# Power_Stage.net
KiCad netlist of a schematic drawn in Altium Designer
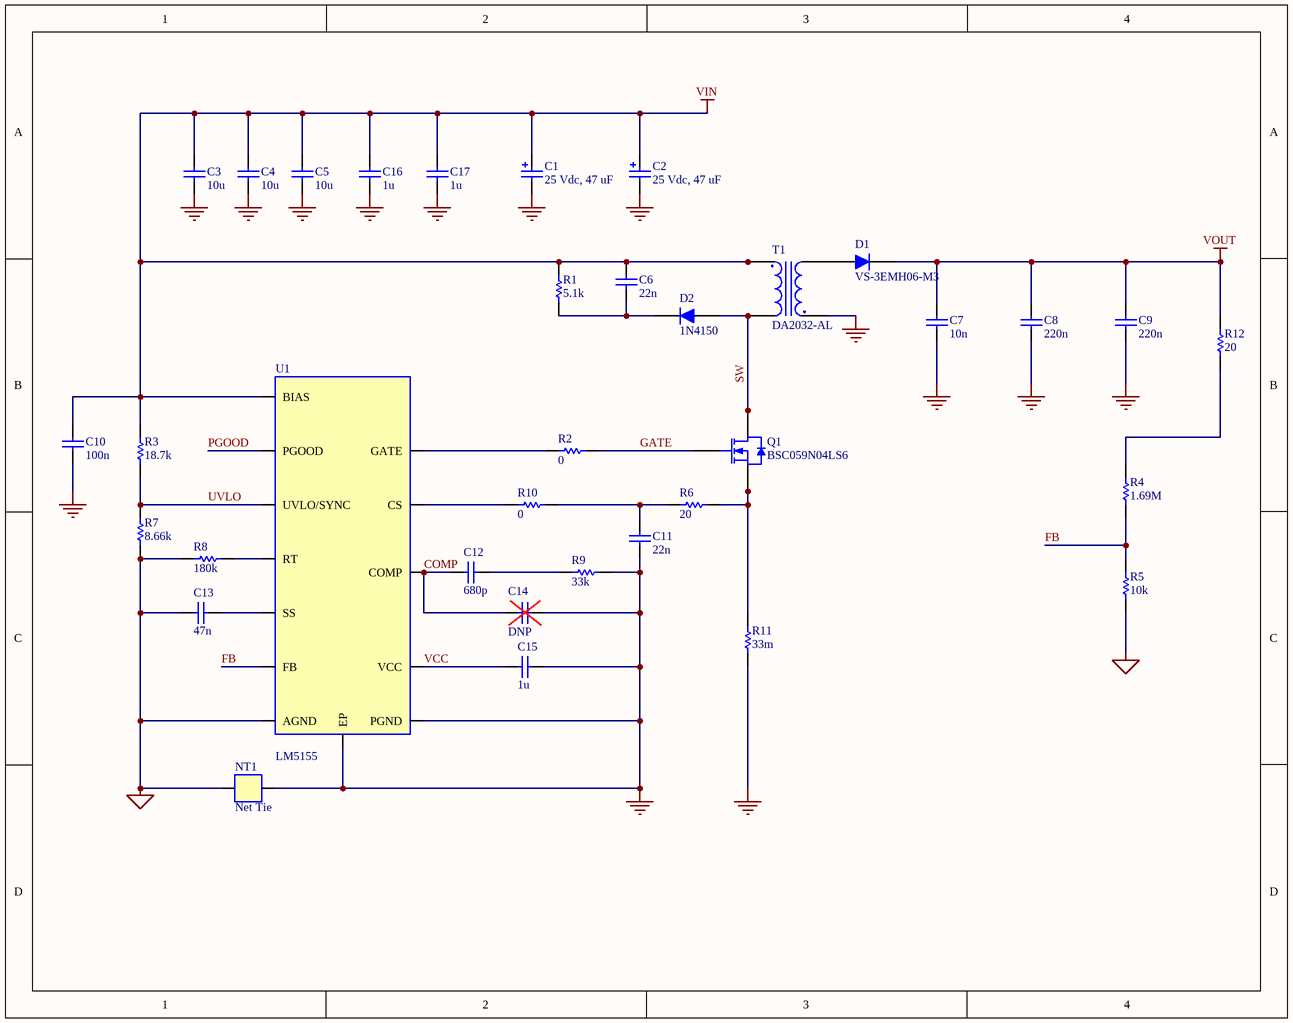
[diagram p0: Power Stage.SchDoc]

(export (version "E")
  (design (tool "Eeschema 10.0.6"))
  (components
    (comp (ref "C1")
      (value "25 Vdc, 47 uF")
      (footprint "WCAP-PTG5_8x8x3.5")
      (description "WCAP-PTG5 Aluminum Polymer Capacitors, 8x8mm, 25 Vdc, 47 uF")
      (fields (field (name "PART NUMBER") "870025574002") (field (name "PUBLISHER") "Wurth Elektronik"))
      (libsource (lib "ALTIUM-WCAP-PTG5-rev17a") (part "870025574002"))
    )
    (comp (ref "C2")
      (value "25 Vdc, 47 uF")
      (footprint "WCAP-PTG5_8x8x3.5")
      (description "WCAP-PTG5 Aluminum Polymer Capacitors, 8x8mm, 25 Vdc, 47 uF")
      (fields (field (name "PART NUMBER") "870025574002") (field (name "PUBLISHER") "Wurth Elektronik"))
      (libsource (lib "ALTIUM-WCAP-PTG5-rev17a") (part "870025574002"))
    )
    (comp (ref "C3")
      (value "10u")
      (footprint "CAPC1210(3225)280_N")
      (description "CAP CER 10UF 50V X7R 1210")
      (fields
        (field (name "MANUFACTURER") "Samsung")
        (field (name "MANUFACTURER PART NUMBER") "CL32B106KBJNNWE")
      )
      (libsource (lib "Misc Caps") (part "CL32B106KBJNNWE"))
    )
    (comp (ref "C4")
      (value "10u")
      (footprint "CAPC1210(3225)280_N")
      (description "CAP CER 10UF 50V X7R 1210")
      (fields
        (field (name "MANUFACTURER") "Samsung")
        (field (name "MANUFACTURER PART NUMBER") "CL32B106KBJNNWE")
      )
      (libsource (lib "Misc Caps") (part "CL32B106KBJNNWE"))
    )
    (comp (ref "C5")
      (value "10u")
      (footprint "CAPC1210(3225)280_N")
      (description "CAP CER 10UF 50V X7R 1210")
      (fields
        (field (name "MANUFACTURER") "Samsung")
        (field (name "MANUFACTURER PART NUMBER") "CL32B106KBJNNWE")
      )
      (libsource (lib "Misc Caps") (part "CL32B106KBJNNWE"))
    )
    (comp (ref "C6")
      (value "22n")
      (footprint "CAPC0805(2012)100_M")
      (description "CAP CER 0.022UF 100V X7R 0805")
      (fields
        (field (name "MANUFACTURER") "Yageo")
        (field (name "MANUFACTURER PART NUMBER") "CC0805KRX7R0BB223")
      )
      (libsource (lib "0805 Caps") (part "CC0805KRX7R0BB223"))
    )
    (comp (ref "C7")
      (value "10n")
      (footprint "CAPC1206(3216)170_M")
      (description "CAP CER 10000PF 250V C0GNP0 1206")
      (fields
        (field (name "MANUFACTURER") "TDK")
        (field (name "MANUFACTURER PART NUMBER") "C3216C0G2E103J115AE")
      )
      (libsource (lib "Misc Caps") (part "C3216C0G2E103J115AE"))
    )
    (comp (ref "C8")
      (value "220n")
      (footprint "WIMA 6x12x13")
      (description "Film Capacitors 250V .22uF 10% PCM10")
      (fields
        (field (name "MANUFACTURER") "WIMA")
        (field (name "MANUFACTURER PART NUMBER") "MKP4F032203G00KSSD")
      )
      (libsource (lib "Misc Caps") (part "MKP4F032203G00KSSD"))
    )
    (comp (ref "C9")
      (value "220n")
      (footprint "WIMA 6x12x13")
      (description "Film Capacitors 250V .22uF 10% PCM10")
      (fields
        (field (name "MANUFACTURER") "WIMA")
        (field (name "MANUFACTURER PART NUMBER") "MKP4F032203G00KSSD")
      )
      (libsource (lib "Misc Caps") (part "MKP4F032203G00KSSD"))
    )
    (comp (ref "C10")
      (value "100n")
      (footprint "CAPC0603(1608)100_N")
      (description "Cap Ceramic 0.1uF 50V X7R 5% SMD 0603 125C Paper T/R")
      (fields
        (field (name "MANUFACTURER") "Yageo")
        (field (name "MANUFACTURER PART NUMBER") "CC0603JRX7R9BB104")
      )
      (libsource (lib "0603 Caps") (part "CC0603JRX7R9BB104"))
    )
    (comp (ref "C11")
      (value "22n")
      (footprint "CAPC0603(1608)100_N")
      (description "Cap Ceramic 0.022uF 16V X7R 10% SMD 0603 125°C Paper T/R")
      (fields
        (field (name "MANUFACTURER") "KEMET")
        (field (name "MANUFACTURER PART NUMBER") "C0603C223K4RACTU")
      )
      (libsource (lib "0603 Caps") (part "C0603C223K4RACTU"))
    )
    (comp (ref "C12")
      (value "680p")
      (footprint "CAPC0603(1608)100_M")
      (description "Cap, Mlcc, C0g, 680Pf, 10V, 0603")
      (fields
        (field (name "MANUFACTURER") "Wurth Electronics")
        (field (name "MANUFACTURER PART NUMBER") "885012006013")
      )
      (libsource (lib "0603 Caps") (part "885012006013"))
    )
    (comp (ref "C13")
      (value "47n")
      (footprint "CAPC0603(1608)100_N")
      (description "CAP CER 0.047UF 50V X7R 0603")
      (fields
        (field (name "MANUFACTURER") "Yageo")
        (field (name "MANUFACTURER PART NUMBER") "CC0603KRX7R9BB473")
      )
      (libsource (lib "0603 Caps") (part "CC0603KRX7R9BB473"))
    )
    (comp (ref "C14")
      (value "DNP")
      (footprint "CAPC0603(1608)100_M")
      (libsource (lib "0603 Caps") (part "0603 DNP JUMPER"))
    )
    (comp (ref "C15")
      (value "1u")
      (footprint "CAPC0603(1608)100_L")
      (description "CAP CER 1UF 16V X7R 0603")
      (fields
        (field (name "MANUFACTURER") "Samsung Electro-Mechanics")
        (field (name "MANUFACTURER PART NUMBER") "CL10B105MO8NNWC")
      )
      (libsource (lib "0603 Caps") (part "CL10B105MO8NNWC"))
    )
    (comp (ref "C16")
      (value "1u")
      (footprint "CAPC0805(2012)145_N")
      (description "Cap Ceramic 1uF 50V X7R 10% SMD 0805 125C Blister T/R")
      (fields
        (field (name "MANUFACTURER") "Yageo")
        (field (name "MANUFACTURER PART NUMBER") "CC0805KKX7R9BB105")
      )
      (libsource (lib "0805 Caps") (part "CC0805KKX7R9BB105"))
    )
    (comp (ref "C17")
      (value "1u")
      (footprint "CAPC0805(2012)145_N")
      (description "Cap Ceramic 1uF 50V X7R 10% SMD 0805 125C Blister T/R")
      (fields
        (field (name "MANUFACTURER") "Yageo")
        (field (name "MANUFACTURER PART NUMBER") "CC0805KKX7R9BB105")
      )
      (libsource (lib "0805 Caps") (part "CC0805KKX7R9BB105"))
    )
    (comp (ref "D1")
      (value "VS-3EMH06-M3")
      (footprint "SMA DO-214AC")
      (description "Rectifiers 3 Amp 600 Volts Hyperfast - Low QRR")
      (fields
        (field (name "MANUFACTURER") "Vishay Semiconductors")
        (field (name "MANUFACTURER PART NUMBER") "VS-3EMH06-M3/5AT")
      )
      (libsource (lib "Discretes") (part "VS-3EMH06-M3/5AT"))
    )
    (comp (ref "D2")
      (value "1N4150")
      (footprint "SOD123")
      (description "DIODE GEN PURP 50V 200MA SOD123")
      (fields
        (field (name "MANUFACTURER") "Vishay Semiconductors")
        (field (name "MANUFACTURER PART NUMBER") "1N4150W-E3-08")
      )
      (libsource (lib "Discretes") (part "1N4150W-E3-08"))
    )
    (comp (ref "NT1")
      (value "Net Tie")
      (footprint "NET TIE .25mm")
      (libsource (lib "Connectors") (part "NET TIE"))
    )
    (comp (ref "Q1")
      (value "BSC059N04LS6")
      (footprint "PG-TDSON-8")
      (description "MOSFET N-CH 40V 59A")
      (fields
        (field (name "MANUFACTURER") "Infineon")
        (field (name "MANUFACTURER PART NUMBER") "BSC059N04LS6ATMA1")
      )
      (libsource (lib "Discretes") (part "BSC059N04LS6ATMA1"))
    )
    (comp (ref "R1")
      (value "5.1k")
      (footprint "RESC1210(3225)_M")
      (description "RES SMD 5.1K OHM 5% 1/2W 1210")
      (fields
        (field (name "MANUFACTURER") "Panasonic")
        (field (name "MANUFACTURER PART NUMBER") "ERJ-14YJ512U")
      )
      (libsource (lib "Misc resistors") (part "ERJ-14YJ512U"))
    )
    (comp (ref "R2")
      (value "0")
      (footprint "RESC0603(1608)_M")
      (description "RES SMD 0 OHM JUMPER 1/10W 0603")
      (fields
        (field (name "MANUFACTURER") "Yageo")
        (field (name "MANUFACTURER PART NUMBER") "RC0603FR-070RL")
      )
      (libsource (lib "0603 Resistors") (part "RC0603FR-070RL"))
    )
    (comp (ref "R3")
      (value "18.7k")
      (footprint "RESC0603(1608)_N")
      (description "RC Series 0603 0.1 W 18.7 kOhms 1% ±100 ppm/°C SMT Thick Film Chip Resistor")
      (fields
        (field (name "MANUFACTURER") "Yageo")
        (field (name "MANUFACTURER PART NUMBER") "RC0603FR-0718K7L")
      )
      (libsource (lib "0603 Resistors") (part "RC0603FR-0718K7L"))
    )
    (comp (ref "R4")
      (value "1.69M")
      (footprint "RESC0603(1608)_N")
      (description "Res Thick Film 0603 1.69M Ohm 1% 1/10W 100ppm/C Molded SMD Paper T/R")
      (fields
        (field (name "MANUFACTURER") "Yageo")
        (field (name "MANUFACTURER PART NUMBER") "RC0603FR-071M69L")
      )
      (libsource (lib "0603 Resistors") (part "RC0603FR-071M69L"))
    )
    (comp (ref "R5")
      (value "10k")
      (footprint "RESC0603(1608)_N")
      (description "RES SMD 10K OHM 1% 1/10W 0603")
      (fields
        (field (name "MANUFACTURER") "Yageo")
        (field (name "MANUFACTURER PART NUMBER") "RC0603FR-0710KL")
      )
      (libsource (lib "0603 Resistors") (part "RC0603FR-0710KL"))
    )
    (comp (ref "R6")
      (value "20")
      (footprint "RESC0603(1608)_N")
      (description "RES SMD 20 OHM 1% 1/10W 0603")
      (fields
        (field (name "MANUFACTURER") "Yageo")
        (field (name "MANUFACTURER PART NUMBER") "RC0603FR-0720RL")
      )
      (libsource (lib "0603 Resistors") (part "RC0603FR-0720RL"))
    )
    (comp (ref "R7")
      (value "8.66k")
      (footprint "RESC0603(1608)_N")
      (description "Res Thick Film 0603 8.66K Ohm 1% 0.1W(1/10W) ±100ppm/C Epoxy Pad SMD T/R")
      (fields
        (field (name "MANUFACTURER") "Yageo")
        (field (name "MANUFACTURER PART NUMBER") "RC0603FR-078K66L")
      )
      (libsource (lib "0603 Resistors") (part "RC0603FR-078K66L"))
    )
    (comp (ref "R8")
      (value "180k")
      (footprint "RESC0603(1608)_N")
      (description "RES SMD 180K OHM 1% 1/10W 0603")
      (fields
        (field (name "MANUFACTURER") "Yageo")
        (field (name "MANUFACTURER PART NUMBER") "RC0603FR-07180KL")
      )
      (libsource (lib "0603 Resistors") (part "RC0603FR-07180KL"))
    )
    (comp (ref "R9")
      (value "33k")
      (footprint "RESC0603(1608)_M")
      (fields
        (field (name "MANUFACTURER") "Yageo")
        (field (name "MANUFACTURER PART NUMBER") "RC0603FR-0733KL")
        (field (name "TOLERANCE") "1%")
      )
      (libsource (lib "0603 Resistors") (part "RC0603FR-0733KL"))
    )
    (comp (ref "R10")
      (value "0")
      (footprint "RESC0603(1608)_M")
      (description "RES SMD 0 OHM JUMPER 1/10W 0603")
      (fields
        (field (name "MANUFACTURER") "Yageo")
        (field (name "MANUFACTURER PART NUMBER") "RC0603FR-070RL")
      )
      (libsource (lib "0603 Resistors") (part "RC0603FR-070RL"))
    )
    (comp (ref "R11")
      (value "33m")
      (footprint "RESC1206(3216)_N")
      (description "TR / Current Sense Resistors 1206 0.75W 0.033ohm 1% 50ppm")
      (fields
        (field (name "MANUFACTURER") "Susumu")
        (field (name "MANUFACTURER PART NUMBER") "KRL1632E-M-R033-F-T5")
      )
      (libsource (lib "Misc resistors") (part "KRL1632E-M-R033-F-T5"))
    )
    (comp (ref "R12")
      (value "20")
      (footprint "RESC0603(1608)_M")
      (description "RES SMD 20 OHM 1% 1/10W 0603")
      (fields
        (field (name "MANUFACTURER") "Yageo")
        (field (name "MANUFACTURER PART NUMBER") "RC0603FR-0720RL")
      )
      (libsource (lib "0603 Resistors") (part "RC0603FR-0720RL"))
    )
    (comp (ref "T1")
      (value "DA2032-AL")
      (footprint "DA2032-AL")
      (description "COILCRAFT - DA2032-ALD - TRANSFORMATOR, FLYBACK, LT3750, SMD")
      (fields
        (field (name "MANUFACTURER") "Coilcraft")
        (field (name "MANUFACTURER PART NUMBER") "DA2032-ALD")
      )
      (libsource (lib "Magnetics") (part "DA2032-ALD"))
    )
    (comp (ref "U1")
      (value "LM5155")
      (footprint "WSON-12")
      (description "2.2MHz wide VIN non-synchronous boost controller 12-WSON -40 to 125")
      (fields
        (field (name "MANUFACTURER") "Texas Instruments")
        (field (name "MANUFACTURER PART NUMBER") "LM5155DSSR")
      )
      (libsource (lib "IC") (part "LM5155DSSR"))
    )
  )
  (nets
    (net (code "1") (name "/COMP") (class "Default")
      (node (ref "C12") (pin "1") (pinfunction "1_1") (pintype "passive"))
      (node (ref "C14") (pin "1") (pinfunction "1_1") (pintype "passive"))
      (node (ref "U1") (pin "6") (pinfunction "COMP_6") (pintype "passive"))
    )
    (net (code "2") (name "/FB") (class "Default")
      (node (ref "R4") (pin "2") (pinfunction "2_2") (pintype "passive"))
      (node (ref "R5") (pin "1") (pinfunction "1_1") (pintype "passive"))
      (node (ref "U1") (pin "8") (pinfunction "FB_8") (pintype "passive"))
    )
    (net (code "3") (name "/GATE") (class "Default")
      (node (ref "Q1") (pin "4") (pinfunction "GATE_4") (pintype "passive"))
      (node (ref "R2") (pin "2") (pinfunction "2_2") (pintype "passive"))
    )
    (net (code "4") (name "/PGOOD") (class "Default")
      (node (ref "U1") (pin "11") (pinfunction "PGOOD_11") (pintype "passive"))
    )
    (net (code "5") (name "/SW") (class "Default")
      (node (ref "D2") (pin "1") (pinfunction "A_1") (pintype "passive"))
      (node (ref "Q1") (pin "5") (pinfunction "DRAIN_5") (pintype "passive"))
      (node (ref "Q1") (pin "6") (pinfunction "DRAIN_6") (pintype "passive"))
      (node (ref "Q1") (pin "7") (pinfunction "DRAIN_7") (pintype "passive"))
      (node (ref "Q1") (pin "8") (pinfunction "DRAIN_8") (pintype "passive"))
      (node (ref "T1") (pin "10") (pinfunction "10_10") (pintype "passive"))
      (node (ref "T1") (pin "7") (pinfunction "7_7") (pintype "passive"))
      (node (ref "T1") (pin "8") (pinfunction "8_8") (pintype "passive"))
      (node (ref "T1") (pin "9") (pinfunction "9_9") (pintype "passive"))
    )
    (net (code "6") (name "/UVLO") (class "Default")
      (node (ref "R3") (pin "1") (pinfunction "1_1") (pintype "passive"))
      (node (ref "R7") (pin "2") (pinfunction "2_2") (pintype "passive"))
      (node (ref "U1") (pin "12") (pinfunction "UVLO/SYNC_12") (pintype "passive"))
    )
    (net (code "7") (name "/VCC") (class "Default")
      (node (ref "C15") (pin "2") (pinfunction "2_2") (pintype "passive"))
      (node (ref "U1") (pin "2") (pinfunction "VCC_2") (pintype "passive"))
    )
    (net (code "8") (name "AGND") (class "Default")
      (node (ref "C13") (pin "2") (pinfunction "2_2") (pintype "passive"))
      (node (ref "NT1") (pin "1") (pintype "passive"))
      (node (ref "R5") (pin "2") (pinfunction "2_2") (pintype "passive"))
      (node (ref "R7") (pin "1") (pinfunction "1_1") (pintype "passive"))
      (node (ref "R8") (pin "1") (pinfunction "1_1") (pintype "passive"))
      (node (ref "U1") (pin "7") (pinfunction "AGND_7") (pintype "passive"))
    )
    (net (code "9") (name "GND") (class "Default")
      (node (ref "C1") (pin "2") (pinfunction "N_2") (pintype "passive"))
      (node (ref "C10") (pin "1") (pinfunction "1_1") (pintype "passive"))
      (node (ref "C11") (pin "1") (pinfunction "1_1") (pintype "passive"))
      (node (ref "C14") (pin "2") (pinfunction "2_2") (pintype "passive"))
      (node (ref "C15") (pin "1") (pinfunction "1_1") (pintype "passive"))
      (node (ref "C16") (pin "1") (pinfunction "1_1") (pintype "passive"))
      (node (ref "C17") (pin "1") (pinfunction "1_1") (pintype "passive"))
      (node (ref "C2") (pin "2") (pinfunction "N_2") (pintype "passive"))
      (node (ref "C3") (pin "1") (pinfunction "1_1") (pintype "passive"))
      (node (ref "C4") (pin "1") (pinfunction "1_1") (pintype "passive"))
      (node (ref "C5") (pin "1") (pinfunction "1_1") (pintype "passive"))
      (node (ref "C7") (pin "1") (pinfunction "1_1") (pintype "passive"))
      (node (ref "C8") (pin "1") (pinfunction "1_1") (pintype "passive"))
      (node (ref "C9") (pin "1") (pinfunction "1_1") (pintype "passive"))
      (node (ref "NT1") (pin "2") (pintype "passive"))
      (node (ref "R11") (pin "1") (pinfunction "1_1") (pintype "passive"))
      (node (ref "R9") (pin "2") (pinfunction "2_2") (pintype "passive"))
      (node (ref "T1") (pin "12") (pinfunction "12_12") (pintype "passive"))
      (node (ref "U1") (pin "13") (pinfunction "EP_13") (pintype "passive"))
      (node (ref "U1") (pin "4") (pinfunction "PGND_4") (pintype "passive"))
    )
    (net (code "10") (name "Net-(C11-Pad2)") (class "Default")
      (node (ref "C11") (pin "2") (pinfunction "2_2") (pintype "passive"))
      (node (ref "R10") (pin "2") (pinfunction "2_2") (pintype "passive"))
      (node (ref "R6") (pin "1") (pinfunction "1_1") (pintype "passive"))
    )
    (net (code "11") (name "Net-(C12-Pad2)") (class "Default")
      (node (ref "C12") (pin "2") (pinfunction "2_2") (pintype "passive"))
      (node (ref "R9") (pin "1") (pinfunction "1_1") (pintype "passive"))
    )
    (net (code "12") (name "Net-(D1-A)") (class "Default")
      (node (ref "D1") (pin "1") (pinfunction "A_1") (pintype "passive"))
      (node (ref "T1") (pin "1") (pinfunction "1_1") (pintype "passive"))
    )
    (net (code "13") (name "Net-(D2-K)") (class "Default")
      (node (ref "C6") (pin "1") (pinfunction "1_1") (pintype "passive"))
      (node (ref "D2") (pin "2") (pinfunction "K_2") (pintype "passive"))
      (node (ref "R1") (pin "1") (pinfunction "1_1") (pintype "passive"))
    )
    (net (code "14") (name "Net-(Q1-SOURCE-Pad1)") (class "Default")
      (node (ref "Q1") (pin "1") (pinfunction "SOURCE_1") (pintype "passive"))
      (node (ref "Q1") (pin "2") (pinfunction "SOURCE_2") (pintype "passive"))
      (node (ref "Q1") (pin "3") (pinfunction "SOURCE_3") (pintype "passive"))
      (node (ref "R11") (pin "2") (pinfunction "2_2") (pintype "passive"))
      (node (ref "R6") (pin "2") (pinfunction "2_2") (pintype "passive"))
    )
    (net (code "15") (name "Net-(R12-Pad1)") (class "Default")
      (node (ref "R12") (pin "1") (pinfunction "1_1") (pintype "passive"))
      (node (ref "R4") (pin "1") (pinfunction "1_1") (pintype "passive"))
    )
    (net (code "16") (name "Net-(U1-CS)") (class "Default")
      (node (ref "R10") (pin "1") (pinfunction "1_1") (pintype "passive"))
      (node (ref "U1") (pin "5") (pinfunction "CS_5") (pintype "passive"))
    )
    (net (code "17") (name "Net-(U1-GATE)") (class "Default")
      (node (ref "R2") (pin "1") (pinfunction "1_1") (pintype "passive"))
      (node (ref "U1") (pin "3") (pinfunction "GATE_3") (pintype "passive"))
    )
    (net (code "18") (name "Net-(U1-RT)") (class "Default")
      (node (ref "R8") (pin "2") (pinfunction "2_2") (pintype "passive"))
      (node (ref "U1") (pin "10") (pinfunction "RT_10") (pintype "passive"))
    )
    (net (code "19") (name "Net-(U1-SS)") (class "Default")
      (node (ref "C13") (pin "1") (pinfunction "1_1") (pintype "passive"))
      (node (ref "U1") (pin "9") (pinfunction "SS_9") (pintype "passive"))
    )
    (net (code "20") (name "VIN") (class "Default")
      (node (ref "C1") (pin "1") (pinfunction "P_1") (pintype "passive"))
      (node (ref "C10") (pin "2") (pinfunction "2_2") (pintype "passive"))
      (node (ref "C16") (pin "2") (pinfunction "2_2") (pintype "passive"))
      (node (ref "C17") (pin "2") (pinfunction "2_2") (pintype "passive"))
      (node (ref "C2") (pin "1") (pinfunction "P_1") (pintype "passive"))
      (node (ref "C3") (pin "2") (pinfunction "2_2") (pintype "passive"))
      (node (ref "C4") (pin "2") (pinfunction "2_2") (pintype "passive"))
      (node (ref "C5") (pin "2") (pinfunction "2_2") (pintype "passive"))
      (node (ref "C6") (pin "2") (pinfunction "2_2") (pintype "passive"))
      (node (ref "R1") (pin "2") (pinfunction "2_2") (pintype "passive"))
      (node (ref "R3") (pin "2") (pinfunction "2_2") (pintype "passive"))
      (node (ref "T1") (pin "3") (pinfunction "3_3") (pintype "passive"))
      (node (ref "T1") (pin "4") (pinfunction "4_4") (pintype "passive"))
      (node (ref "T1") (pin "5") (pinfunction "5_5") (pintype "passive"))
      (node (ref "T1") (pin "6") (pinfunction "6_6") (pintype "passive"))
      (node (ref "U1") (pin "1") (pinfunction "BIAS_1") (pintype "passive"))
    )
    (net (code "21") (name "VOUT") (class "Default")
      (node (ref "C7") (pin "2") (pinfunction "2_2") (pintype "passive"))
      (node (ref "C8") (pin "2") (pinfunction "2_2") (pintype "passive"))
      (node (ref "C9") (pin "2") (pinfunction "2_2") (pintype "passive"))
      (node (ref "D1") (pin "2") (pinfunction "K_2") (pintype "passive"))
      (node (ref "R12") (pin "2") (pinfunction "2_2") (pintype "passive"))
    )
  )
)
